# aig2.net
KiCad netlist of a schematic drawn in Altium Designer
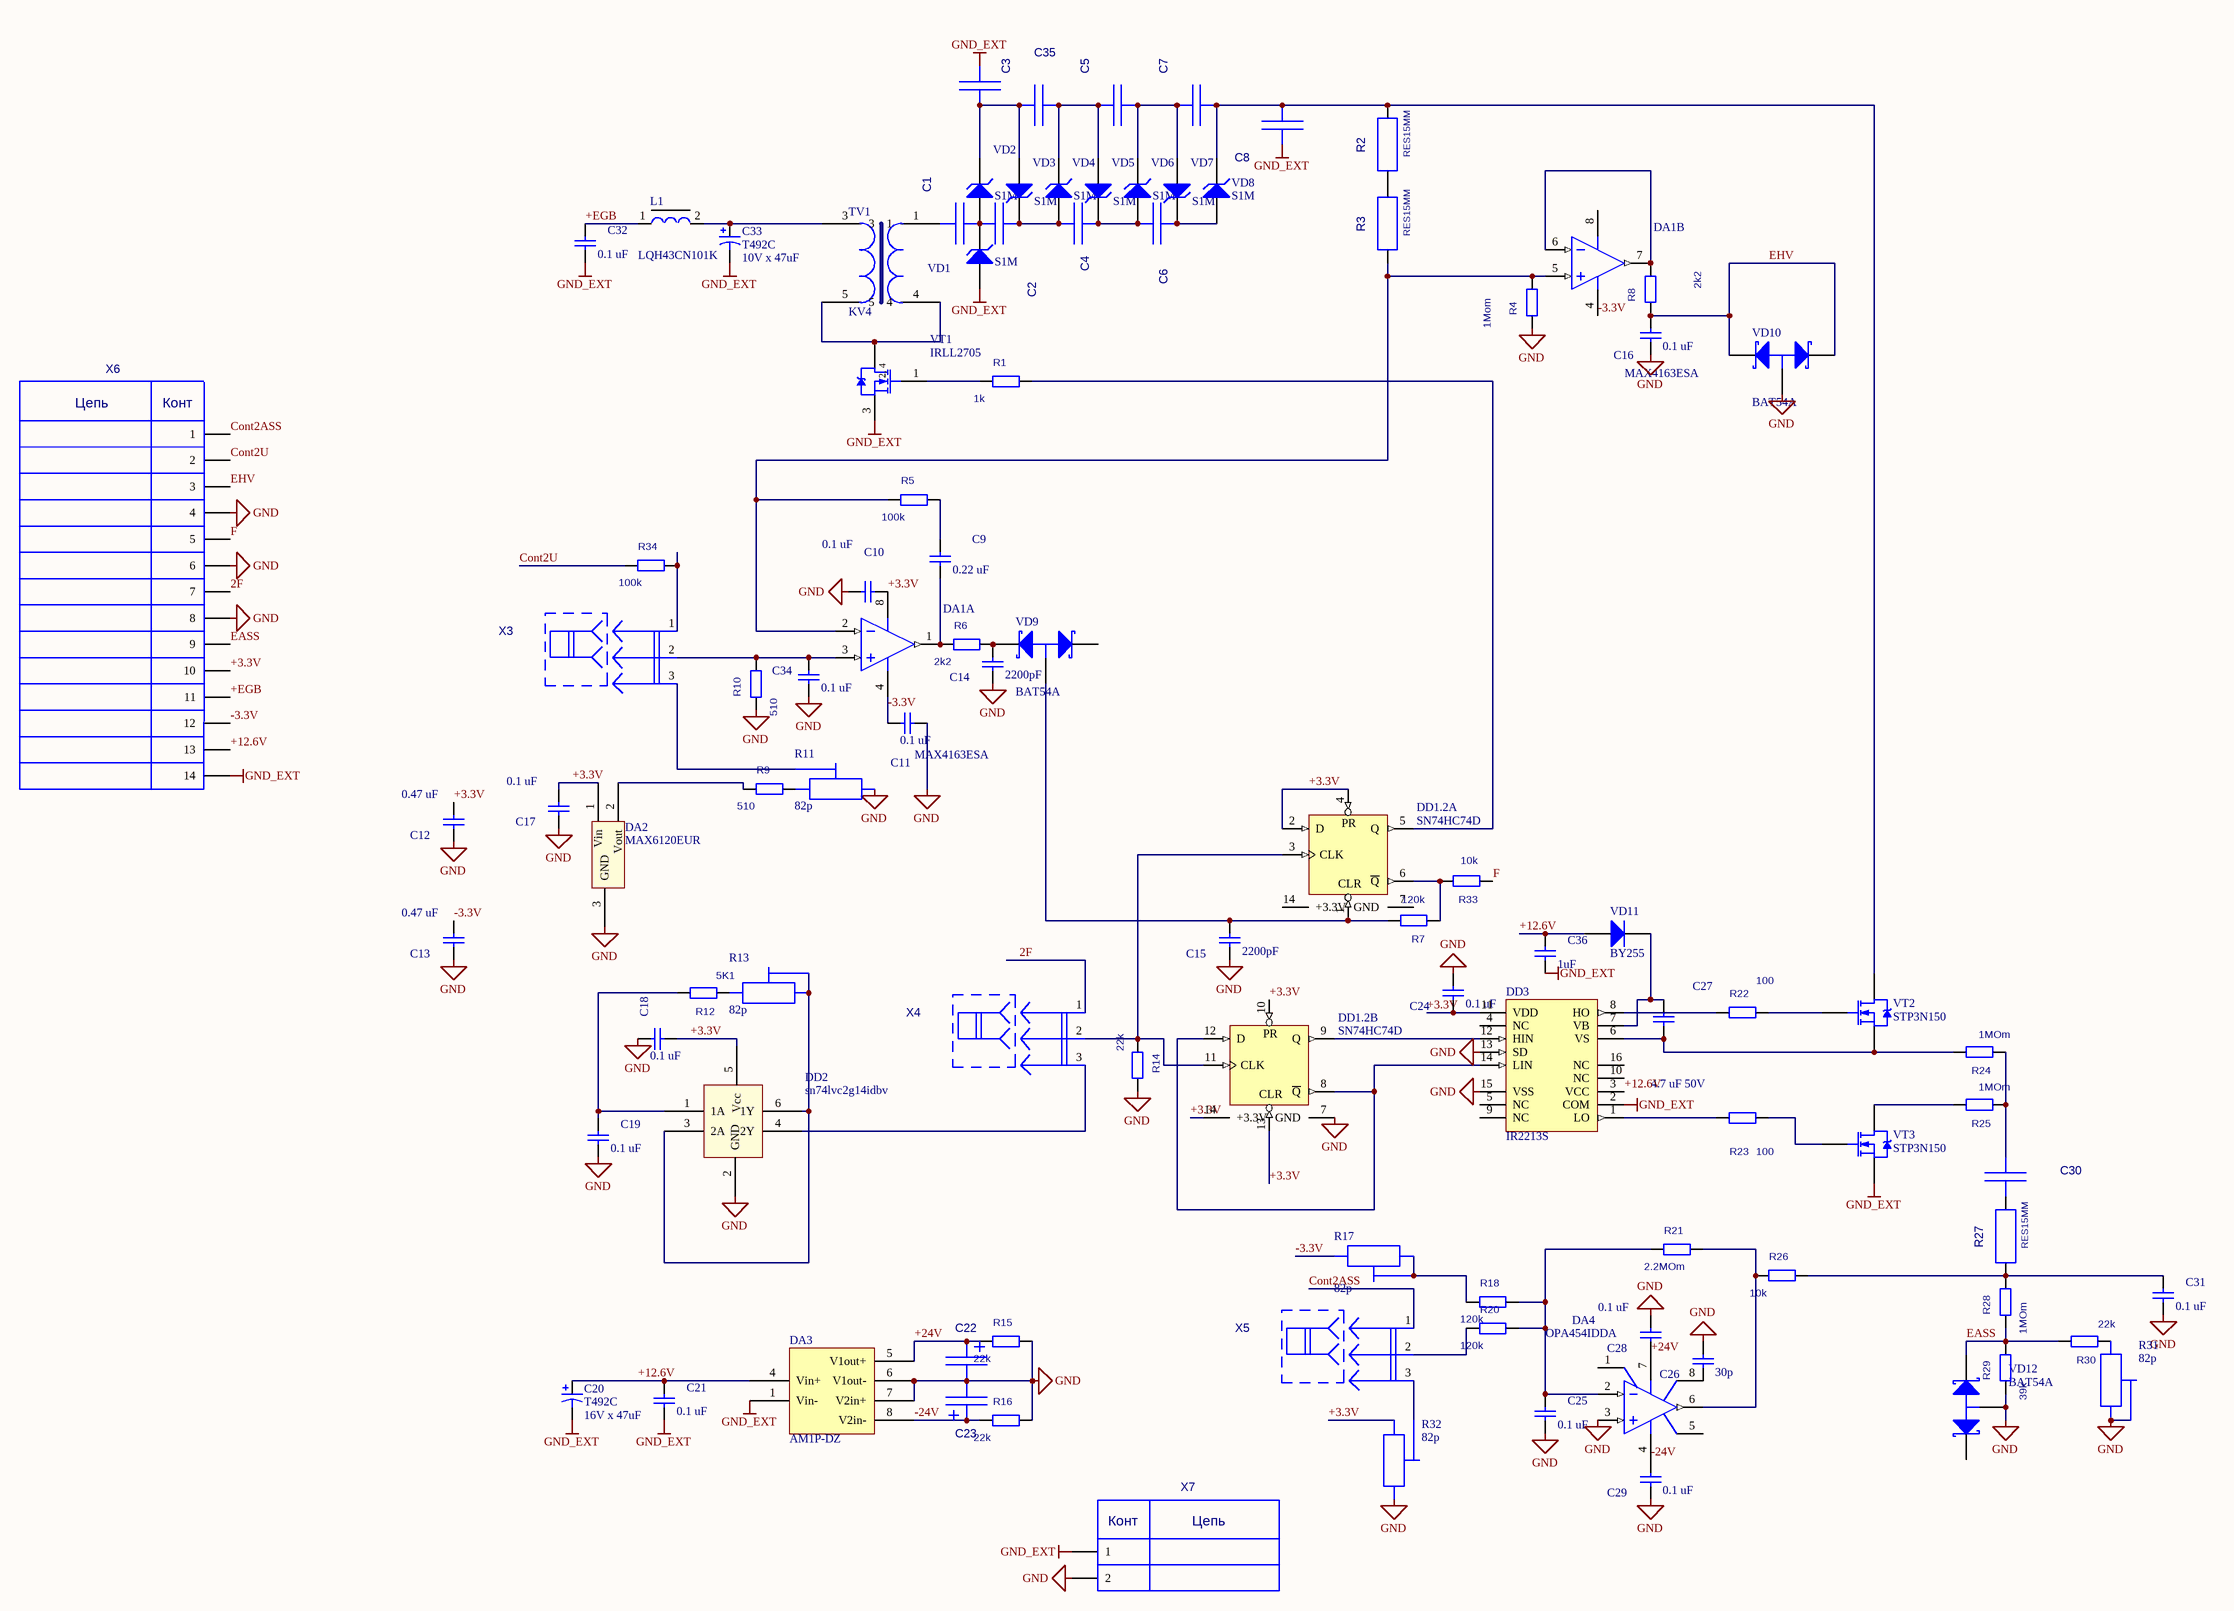
[diagram p0: aig2.SchDoc]

(export (version "E")
  (design (tool "Eeschema 10.0.6"))
  (components
    (comp (ref "C1") (value "CC1812") (footprint "CC1812") (libsource (lib "MyElements") (part "CC1812")))
    (comp (ref "C2") (value "CC1812") (footprint "CC1812") (libsource (lib "MyElements") (part "CC1812")))
    (comp (ref "C3") (value "CC1812") (footprint "CC1812") (libsource (lib "MyElements") (part "CC1812")))
    (comp (ref "C4") (value "CC1812") (footprint "CC1812") (libsource (lib "MyElements") (part "CC1812")))
    (comp (ref "C5") (value "CC1812") (footprint "CC1812") (libsource (lib "MyElements") (part "CC1812")))
    (comp (ref "C6") (value "CC1812") (footprint "CC1812") (libsource (lib "MyElements") (part "CC1812")))
    (comp (ref "C7") (value "CC1812") (footprint "CC1812") (libsource (lib "MyElements") (part "CC1812")))
    (comp (ref "C8") (value "CC1812") (footprint "CC1812") (libsource (lib "MyElements") (part "CC1812")))
    (comp (ref "C9")
      (value "0.22 uF")
      (footprint "CC0805")
      (description "Ceramic Chip Capacitor - Standard")
      (fields (field (name "Comment") "C0805") (field (name "PUBLISHER") "Altium Limited"))
      (libsource (lib "KEMET Chip Capacitor") (part "C0805"))
    )
    (comp (ref "C10")
      (value "0.1 uF")
      (footprint "CC0805")
      (description "Ceramic Chip Capacitor - Standard")
      (fields (field (name "Comment") "C0805") (field (name "PUBLISHER") "Altium Limited"))
      (libsource (lib "KEMET Chip Capacitor") (part "C0805"))
    )
    (comp (ref "C11")
      (value "0.1 uF")
      (footprint "CC0805")
      (description "Ceramic Chip Capacitor - Standard")
      (fields (field (name "Comment") "C0805") (field (name "PUBLISHER") "Altium Limited"))
      (libsource (lib "KEMET Chip Capacitor") (part "C0805"))
    )
    (comp (ref "C12")
      (value "0.47 uF")
      (footprint "CC0805")
      (description "Ceramic Chip Capacitor - Standard")
      (fields (field (name "Comment") "C0805") (field (name "PUBLISHER") "Altium Limited"))
      (libsource (lib "KEMET Chip Capacitor") (part "C0805"))
    )
    (comp (ref "C13")
      (value "0.47 uF")
      (footprint "CC0805")
      (description "Ceramic Chip Capacitor - Standard")
      (fields (field (name "Comment") "C0805") (field (name "PUBLISHER") "Altium Limited"))
      (libsource (lib "KEMET Chip Capacitor") (part "C0805"))
    )
    (comp (ref "C14")
      (value "2200pF")
      (footprint "CC0805")
      (description "Ceramic Chip Capacitor - Standard")
      (fields (field (name "Comment") "C0805") (field (name "PUBLISHER") "Altium Limited"))
      (libsource (lib "KEMET Chip Capacitor") (part "C0805"))
    )
    (comp (ref "C15")
      (value "2200pF")
      (footprint "CC0805")
      (description "Ceramic Chip Capacitor - Standard")
      (fields (field (name "Comment") "C0805") (field (name "PUBLISHER") "Altium Limited"))
      (libsource (lib "KEMET Chip Capacitor") (part "C0805"))
    )
    (comp (ref "C16")
      (value "0.1 uF")
      (footprint "CC0805")
      (description "Ceramic Chip Capacitor - Standard")
      (fields (field (name "Comment") "C0805") (field (name "PUBLISHER") "Altium Limited"))
      (libsource (lib "KEMET Chip Capacitor") (part "C0805"))
    )
    (comp (ref "C17")
      (value "0.1 uF")
      (footprint "CC0805")
      (description "Ceramic Chip Capacitor - Standard")
      (fields (field (name "Comment") "C0805") (field (name "PUBLISHER") "Altium Limited"))
      (libsource (lib "KEMET Chip Capacitor") (part "C0805"))
    )
    (comp (ref "C18")
      (value "0.1 uF")
      (footprint "CC0805")
      (description "Ceramic Chip Capacitor - Standard")
      (fields (field (name "Comment") "C0805") (field (name "PUBLISHER") "Altium Limited"))
      (libsource (lib "KEMET Chip Capacitor") (part "C0805"))
    )
    (comp (ref "C19")
      (value "0.1 uF")
      (footprint "CC0805")
      (description "Ceramic Chip Capacitor - Standard")
      (fields (field (name "Comment") "C0805") (field (name "PUBLISHER") "Altium Limited"))
      (libsource (lib "KEMET Chip Capacitor") (part "C0805"))
    )
    (comp (ref "C20")
      (value "T492C")
      (footprint "CAPASITOR C")
      (description "Solid Tantalum Chip Capacitor, T492 Series - CWR11 Style Per Mil-PRF-55365/8")
      (fields (field (name "ALTIUM_VALUE") "16V x 47uF") (field (name "PUBLISHER") "Altium Limited"))
      (libsource (lib "KEMET Chip Capacitor") (part "T492C"))
    )
    (comp (ref "C21")
      (value "0.1 uF")
      (footprint "CC0805")
      (description "Ceramic Chip Capacitor - Standard")
      (fields (field (name "Comment") "C0805") (field (name "PUBLISHER") "Altium Limited"))
      (libsource (lib "KEMET Chip Capacitor") (part "C0805"))
    )
    (comp (ref "C22")
      (value "CAPASITOR A")
      (footprint "CAPASITOR A")
      (libsource (lib "MyElements") (part "CAPASITOR A"))
    )
    (comp (ref "C23")
      (value "CAPASITOR A")
      (footprint "CAPASITOR A")
      (libsource (lib "MyElements") (part "CAPASITOR A"))
    )
    (comp (ref "C24")
      (value "0.1 uF")
      (footprint "CC0805")
      (description "Ceramic Chip Capacitor - Standard")
      (fields (field (name "Comment") "C0805") (field (name "PUBLISHER") "Altium Limited"))
      (libsource (lib "KEMET Chip Capacitor") (part "C0805"))
    )
    (comp (ref "C25")
      (value "0.1 uF")
      (footprint "CC0805")
      (description "Ceramic Chip Capacitor - Standard")
      (fields (field (name "Comment") "C0805") (field (name "PUBLISHER") "Altium Limited"))
      (libsource (lib "KEMET Chip Capacitor") (part "C0805"))
    )
    (comp (ref "C26")
      (value "30p")
      (footprint "CC0805")
      (description "Ceramic Chip Capacitor - Standard")
      (fields (field (name "Comment") "C0805") (field (name "PUBLISHER") "Altium Limited"))
      (libsource (lib "KEMET Chip Capacitor") (part "C0805"))
    )
    (comp (ref "C27")
      (value "4.7 uF 50V")
      (footprint "CC0805")
      (description "Ceramic Chip Capacitor - Standard")
      (fields (field (name "Comment") "C0805") (field (name "PUBLISHER") "Altium Limited"))
      (libsource (lib "KEMET Chip Capacitor") (part "C0805"))
    )
    (comp (ref "C28")
      (value "0.1 uF")
      (footprint "CC0805")
      (description "Ceramic Chip Capacitor - Standard")
      (fields (field (name "Comment") "C0805") (field (name "PUBLISHER") "Altium Limited"))
      (libsource (lib "KEMET Chip Capacitor") (part "C0805"))
    )
    (comp (ref "C29")
      (value "0.1 uF")
      (footprint "CC0805")
      (description "Ceramic Chip Capacitor - Standard")
      (fields (field (name "Comment") "C0805") (field (name "PUBLISHER") "Altium Limited"))
      (libsource (lib "KEMET Chip Capacitor") (part "C0805"))
    )
    (comp (ref "C30") (value "CC1812") (footprint "CC1812") (libsource (lib "MyElements") (part "CC1812")))
    (comp (ref "C31")
      (value "0.1 uF")
      (footprint "CC0805")
      (description "Ceramic Chip Capacitor - Standard")
      (fields (field (name "Comment") "C0805") (field (name "PUBLISHER") "Altium Limited"))
      (libsource (lib "KEMET Chip Capacitor") (part "C0805"))
    )
    (comp (ref "C32")
      (value "0.1 uF")
      (footprint "CC0805")
      (description "Ceramic Chip Capacitor - Standard")
      (fields (field (name "Comment") "C0805") (field (name "PUBLISHER") "Altium Limited"))
      (libsource (lib "KEMET Chip Capacitor") (part "C0805"))
    )
    (comp (ref "C33")
      (value "T492C")
      (footprint "CAPASITOR C")
      (description "Solid Tantalum Chip Capacitor, T492 Series - CWR11 Style Per Mil-PRF-55365/8")
      (fields (field (name "ALTIUM_VALUE") "10V x 47uF") (field (name "PUBLISHER") "Altium Limited"))
      (libsource (lib "KEMET Chip Capacitor") (part "T492C"))
    )
    (comp (ref "C34")
      (value "0.1 uF")
      (footprint "CC0805")
      (description "Ceramic Chip Capacitor - Standard")
      (fields (field (name "Comment") "C0805") (field (name "PUBLISHER") "Altium Limited"))
      (libsource (lib "KEMET Chip Capacitor") (part "C0805"))
    )
    (comp (ref "C35") (value "CC1812") (footprint "CC1812") (libsource (lib "MyElements") (part "CC1812")))
    (comp (ref "C36")
      (value "1uF")
      (footprint "CC0805")
      (description "Ceramic Chip Capacitor - Standard")
      (fields (field (name "Comment") "C0805") (field (name "PUBLISHER") "Altium Limited"))
      (libsource (lib "KEMET Chip Capacitor") (part "C0805"))
    )
    (comp (ref "DA1")
      (value "MAX4163ESA")
      (footprint "NSO8_N")
      (description "Dual Micropower, Single-Supply, Rail-to-Rail I/O Op Amp")
      (fields (field (name "PUBLISHER") "Altium Limited"))
      (libsource (lib "Maxim Operational Amplifier") (part "MAX4163ESA"))
    )
    (comp (ref "DA2")
      (value "MAX6120EUR")
      (footprint "sot23")
      (description "Микросхема")
      (libsource (lib "lgar") (part "MAX6120"))
    )
    (comp (ref "DA3")
      (value "AM1P-DZ")
      (footprint "Am1p")
      (description "DC/DC Перобразователь")
      (libsource (lib "lgar") (part "AM1P-DZ"))
    )
    (comp (ref "DA4")
      (value "OPA454IDDA")
      (footprint "182H_N")
      (description "Ultra-Low-Noise Precision Operational Amplifiers")
      (fields (field (name "PUBLISHER") "Altium Limited"))
      (libsource (lib "BB Operational Amplifier") (part "OPA27GU"))
    )
    (comp (ref "DD1.2")
      (value "SN74HC74D")
      (footprint "D014_N")
      (description "Dual D-Type Positive-Edge-Triggered Flip-Flop with Clear and Preset")
      (fields (field (name "PUBLISHER") "Altium Limited"))
      (libsource (lib "TI Logic Flip-Flop") (part "SN74HC74D"))
    )
    (comp (ref "DD2")
      (value "sn74lvc2g14idbv")
      (footprint "sot23-6_N")
      (description "Микросхема")
      (libsource (lib "lgar") (part "sn74lvc2g14idbv"))
    )
    (comp (ref "DD3")
      (value "IR2213S")
      (footprint "SOIC16_N")
      (description "High and Low Side Driver")
      (fields (field (name "PUBLISHER") "Altium Limited"))
      (libsource (lib "IR Interface Bridge Driver") (part "IR2113S"))
    )
    (comp (ref "L1")
      (value "LQH43CN101K")
      (footprint "1812")
      (description "Дроссель")
      (libsource (lib "lgar") (part "CDRH127"))
    )
    (comp (ref "R1")
      (value "1k")
      (footprint "RR0805")
      (description "R_0805")
      (libsource (lib "*") (part "R_0805"))
    )
    (comp (ref "R2") (value "RES15MM") (footprint "RES15MM") (libsource (lib "MyElements") (part "RES15MM")))
    (comp (ref "R3") (value "RES15MM") (footprint "RES15MM") (libsource (lib "MyElements") (part "RES15MM")))
    (comp (ref "R4")
      (value "1Mom")
      (footprint "RR0805")
      (description "R_0805")
      (libsource (lib "*") (part "R_0805"))
    )
    (comp (ref "R5")
      (value "100k")
      (footprint "RR0805")
      (description "R_0805")
      (libsource (lib "*") (part "R_0805"))
    )
    (comp (ref "R6")
      (value "2k2")
      (footprint "RR0805")
      (description "R_0805")
      (libsource (lib "*") (part "R_0805"))
    )
    (comp (ref "R7")
      (value "120k")
      (footprint "RR0805")
      (description "R_0805")
      (libsource (lib "*") (part "R_0805"))
    )
    (comp (ref "R8")
      (value "2k2")
      (footprint "RR0805")
      (description "R_0805")
      (libsource (lib "*") (part "R_0805"))
    )
    (comp (ref "R9")
      (value "510")
      (footprint "RR0805")
      (description "R_0805")
      (libsource (lib "*") (part "R_0805"))
    )
    (comp (ref "R10")
      (value "510")
      (footprint "RR0805")
      (description "R_0805")
      (libsource (lib "*") (part "R_0805"))
    )
    (comp (ref "R11")
      (value "82p")
      (footprint "82p")
      (description "Резистор")
      (libsource (lib "lgar") (part "82p"))
    )
    (comp (ref "R12")
      (value "5K1")
      (footprint "RR0805")
      (description "R_0805")
      (libsource (lib "*") (part "R_0805"))
    )
    (comp (ref "R13")
      (value "82p")
      (footprint "82p")
      (description "Резистор")
      (libsource (lib "lgar") (part "82p"))
    )
    (comp (ref "R14")
      (value "22k")
      (footprint "RR0805")
      (description "R_0805")
      (libsource (lib "*") (part "R_0805"))
    )
    (comp (ref "R15")
      (value "22k")
      (footprint "RR0805")
      (description "R_0805")
      (libsource (lib "*") (part "R_0805"))
    )
    (comp (ref "R16")
      (value "22k")
      (footprint "RR0805")
      (description "R_0805")
      (libsource (lib "*") (part "R_0805"))
    )
    (comp (ref "R17")
      (value "82p")
      (footprint "82p")
      (description "Резистор")
      (libsource (lib "lgar") (part "82p"))
    )
    (comp (ref "R18")
      (value "120k")
      (footprint "RR0805")
      (description "R_0805")
      (libsource (lib "*") (part "R_0805"))
    )
    (comp (ref "R20")
      (value "120k")
      (footprint "RR0805")
      (description "R_0805")
      (libsource (lib "*") (part "R_0805"))
    )
    (comp (ref "R21")
      (value "2.2MOm")
      (footprint "RR0805")
      (description "R_0805")
      (libsource (lib "*") (part "R_0805"))
    )
    (comp (ref "R22")
      (value "100")
      (footprint "RR0805")
      (description "R_0805")
      (libsource (lib "*") (part "R_0805"))
    )
    (comp (ref "R23")
      (value "100")
      (footprint "RR0805")
      (description "R_0805")
      (libsource (lib "*") (part "R_0805"))
    )
    (comp (ref "R24")
      (value "1MOm")
      (footprint "RR0805")
      (description "R_0805")
      (libsource (lib "*") (part "R_0805"))
    )
    (comp (ref "R25")
      (value "1MOm")
      (footprint "RR0805")
      (description "R_0805")
      (libsource (lib "*") (part "R_0805"))
    )
    (comp (ref "R26")
      (value "10k")
      (footprint "RR0805")
      (description "R_0805")
      (libsource (lib "*") (part "R_0805"))
    )
    (comp (ref "R27") (value "RES15MM") (footprint "RES15MM") (libsource (lib "MyElements") (part "RES15MM")))
    (comp (ref "R28")
      (value "1MOm")
      (footprint "RR0805")
      (description "R_0805")
      (libsource (lib "*") (part "R_0805"))
    )
    (comp (ref "R29")
      (value "39k")
      (footprint "RR0805")
      (description "R_0805")
      (libsource (lib "*") (part "R_0805"))
    )
    (comp (ref "R30")
      (value "22k")
      (footprint "RR0805")
      (description "R_0805")
      (libsource (lib "*") (part "R_0805"))
    )
    (comp (ref "R31")
      (value "82p")
      (footprint "82p")
      (description "Резистор")
      (libsource (lib "lgar") (part "82p"))
    )
    (comp (ref "R32")
      (value "82p")
      (footprint "82p")
      (description "Резистор")
      (libsource (lib "lgar") (part "82p"))
    )
    (comp (ref "R33")
      (value "10k")
      (footprint "RR0805")
      (description "R_0805")
      (libsource (lib "*") (part "R_0805"))
    )
    (comp (ref "R34")
      (value "100k")
      (footprint "RR0805")
      (description "R_0805")
      (libsource (lib "*") (part "R_0805"))
    )
    (comp (ref "TV1")
      (value "KV4")
      (footprint "kv4")
      (description "Трансформатор")
      (libsource (lib "lgar") (part "KV4"))
    )
    (comp (ref "VD1")
      (value "S1M")
      (footprint "DO214")
      (description "Silicon Zener Diode (3W)")
      (fields (field (name "PUBLISHER") "Altium Limited"))
      (libsource (lib "Vishay Telefunken Discrete Diode") (part "BZG03C10"))
    )
    (comp (ref "VD2")
      (value "S1M")
      (footprint "DO214")
      (description "Silicon Zener Diode (3W)")
      (fields (field (name "PUBLISHER") "Altium Limited"))
      (libsource (lib "Vishay Telefunken Discrete Diode") (part "BZG03C10"))
    )
    (comp (ref "VD3")
      (value "S1M")
      (footprint "DO214")
      (description "Silicon Zener Diode (3W)")
      (fields (field (name "PUBLISHER") "Altium Limited"))
      (libsource (lib "Vishay Telefunken Discrete Diode") (part "BZG03C10"))
    )
    (comp (ref "VD4")
      (value "S1M")
      (footprint "DO214")
      (description "Silicon Zener Diode (3W)")
      (fields (field (name "PUBLISHER") "Altium Limited"))
      (libsource (lib "Vishay Telefunken Discrete Diode") (part "BZG03C10"))
    )
    (comp (ref "VD5")
      (value "S1M")
      (footprint "DO214")
      (description "Silicon Zener Diode (3W)")
      (fields (field (name "PUBLISHER") "Altium Limited"))
      (libsource (lib "Vishay Telefunken Discrete Diode") (part "BZG03C10"))
    )
    (comp (ref "VD6")
      (value "S1M")
      (footprint "DO214")
      (description "Silicon Zener Diode (3W)")
      (fields (field (name "PUBLISHER") "Altium Limited"))
      (libsource (lib "Vishay Telefunken Discrete Diode") (part "BZG03C10"))
    )
    (comp (ref "VD7")
      (value "S1M")
      (footprint "DO214")
      (description "Silicon Zener Diode (3W)")
      (fields (field (name "PUBLISHER") "Altium Limited"))
      (libsource (lib "Vishay Telefunken Discrete Diode") (part "BZG03C10"))
    )
    (comp (ref "VD8")
      (value "S1M")
      (footprint "DO214")
      (description "Silicon Zener Diode (3W)")
      (fields (field (name "PUBLISHER") "Altium Limited"))
      (libsource (lib "Vishay Telefunken Discrete Diode") (part "BZG03C10"))
    )
    (comp (ref "VD9")
      (value "BAT54A")
      (footprint "SOT23_N")
      (description "Schottky Barrier Double Diode")
      (fields (field (name "PUBLISHER") "Altium Limited"))
      (libsource (lib "Philips Discrete Diode - Schottky") (part "BAT54A"))
    )
    (comp (ref "VD10")
      (value "BAT54A")
      (footprint "SOT23_N")
      (description "Schottky Barrier Double Diode")
      (fields (field (name "PUBLISHER") "Altium Limited"))
      (libsource (lib "Philips Discrete Diode - Schottky") (part "BAT54A"))
    )
    (comp (ref "VD11")
      (value "BY255")
      (footprint "SOD27")
      (description "Диод")
      (fields (field (name "PUBLISHER") "Altium Limited"))
      (libsource (lib "Philips Discrete Diode - Switching") (part "BZX79-B15"))
    )
    (comp (ref "VD12")
      (value "BAT54A")
      (footprint "SOT23_N")
      (description "Schottky Barrier Double Diode")
      (fields (field (name "PUBLISHER") "Altium Limited"))
      (libsource (lib "Philips Discrete Diode - Schottky") (part "BAT54A"))
    )
    (comp (ref "VT1")
      (value "IRLL2705")
      (footprint "SOT-223")
      (description "HEXFET Power MOSFET")
      (fields (field (name "PUBLISHER") "Altium Limited"))
      (libsource (lib "IR Discrete MOSFET - Power") (part "IRLL2705"))
    )
    (comp (ref "VT2")
      (value "STP3N150")
      (footprint "TO-220AB")
      (description "HEXFET N-Channel Power MOSFET")
      (fields (field (name "PUBLISHER") "Altium Limited"))
      (libsource (lib "IR Discrete MOSFET - Power") (part "IRF740"))
    )
    (comp (ref "VT3")
      (value "STP3N150")
      (footprint "TO-220AB")
      (description "HEXFET N-Channel Power MOSFET")
      (fields (field (name "PUBLISHER") "Altium Limited"))
      (libsource (lib "IR Discrete MOSFET - Power") (part "IRF740"))
    )
    (comp (ref "X3") (value "JP3") (footprint "PLS-3 2.54") (libsource (lib "MyElements") (part "JP3")))
    (comp (ref "X4") (value "JP3") (footprint "PLS-3 2.54") (libsource (lib "MyElements") (part "JP3")))
    (comp (ref "X5") (value "JP3") (footprint "PLS-3 2.54") (libsource (lib "MyElements") (part "JP3")))
    (comp (ref "X6") (value "IDC14M") (footprint "IDC14M") (libsource (lib "MyElements") (part "IDC14M")))
    (comp (ref "X7") (value "PLS-2") (footprint "PLS-2 2.54") (libsource (lib "MyElements") (part "PLS-2")))
  )
  (nets
    (net (code "1") (name "/+3.3V") (class "Default")
      (node (ref "C10") (pin "2") (pinfunction "2_2") (pintype "passive"))
      (node (ref "C12") (pin "1") (pinfunction "1_1") (pintype "passive"))
      (node (ref "C17") (pin "1") (pinfunction "1_1") (pintype "passive"))
      (node (ref "C18") (pin "1") (pinfunction "1_1") (pintype "passive"))
      (node (ref "C24") (pin "2") (pinfunction "2_2") (pintype "passive"))
      (node (ref "DA1") (pin "8") (pinfunction "VDD_8") (pintype "power_in"))
      (node (ref "DA2") (pin "1") (pinfunction "Vin_1") (pintype "passive"))
      (node (ref "DD1.2") (pin "10") (pinfunction "PR_10") (pintype "input"))
      (node (ref "DD1.2") (pin "13") (pinfunction "CLR_13") (pintype "input"))
      (node (ref "DD1.2") (pin "14") (pinfunction "+3.3V_14") (pintype "power_in"))
      (node (ref "DD1.2") (pin "2") (pinfunction "D_2") (pintype "input"))
      (node (ref "DD1.2") (pin "4") (pinfunction "PR_4") (pintype "input"))
      (node (ref "DD2") (pin "5") (pinfunction "Vcc_5") (pintype "passive"))
      (node (ref "DD3") (pin "11") (pinfunction "VDD_11") (pintype "power_in"))
      (node (ref "R32") (pin "1") (pinfunction "I/O1_1") (pintype "passive"))
      (node (ref "X6") (pin "10") (pinfunction "10_10") (pintype "passive"))
    )
    (net (code "2") (name "/+12.6V") (class "Default")
      (node (ref "C20") (pin "1") (pinfunction "1_1") (pintype "passive"))
      (node (ref "C21") (pin "2") (pinfunction "2_2") (pintype "passive"))
      (node (ref "C36") (pin "2") (pinfunction "2_2") (pintype "passive"))
      (node (ref "DA3") (pin "4") (pinfunction "Vin+_4") (pintype "power_in"))
      (node (ref "DD3") (pin "3") (pinfunction "VCC_3") (pintype "power_in"))
      (node (ref "VD11") (pin "1") (pinfunction "A_1") (pintype "passive"))
      (node (ref "X6") (pin "13") (pinfunction "13_13") (pintype "passive"))
    )
    (net (code "3") (name "/+24V") (class "Default")
      (node (ref "C22") (pin "1") (pinfunction "i/o_1") (pintype "passive"))
      (node (ref "C28") (pin "2") (pinfunction "2_2") (pintype "passive"))
      (node (ref "DA3") (pin "5") (pinfunction "V1out+_5") (pintype "power_in"))
      (node (ref "DA4") (pin "7") (pinfunction "V+_7") (pintype "power_in"))
      (node (ref "R15") (pin "1") (pintype "passive"))
    )
    (net (code "4") (name "/+EGB") (class "Default")
      (node (ref "C32") (pin "2") (pinfunction "2_2") (pintype "passive"))
      (node (ref "L1") (pin "1") (pinfunction "1_1") (pintype "passive"))
      (node (ref "X6") (pin "11") (pinfunction "11_11") (pintype "passive"))
    )
    (net (code "5") (name "/-3.3V") (class "Default")
      (node (ref "C11") (pin "2") (pinfunction "2_2") (pintype "passive"))
      (node (ref "C13") (pin "1") (pinfunction "1_1") (pintype "passive"))
      (node (ref "DA1") (pin "4") (pinfunction "VSS_4") (pintype "power_in"))
      (node (ref "R17") (pin "3") (pinfunction "I/O_3") (pintype "passive"))
      (node (ref "X6") (pin "12") (pinfunction "12_12") (pintype "passive"))
    )
    (net (code "6") (name "/-24V") (class "Default")
      (node (ref "C23") (pin "1") (pinfunction "i/o_1") (pintype "passive"))
      (node (ref "C29") (pin "1") (pinfunction "1_1") (pintype "passive"))
      (node (ref "DA3") (pin "8") (pinfunction "V2in-_8") (pintype "power_in"))
      (node (ref "DA4") (pin "4") (pinfunction "V-_4") (pintype "power_in"))
      (node (ref "R16") (pin "1") (pintype "passive"))
    )
    (net (code "7") (name "/2F") (class "Default")
      (node (ref "X4") (pin "1") (pinfunction "I/O1_1") (pintype "passive"))
      (node (ref "X6") (pin "7") (pinfunction "7_7") (pintype "passive"))
    )
    (net (code "8") (name "/Cont2ASS") (class "Default")
      (node (ref "X5") (pin "1") (pinfunction "I/O1_1") (pintype "passive"))
      (node (ref "X6") (pin "1") (pinfunction "1_1") (pintype "passive"))
    )
    (net (code "9") (name "/Cont2U") (class "Default")
      (node (ref "R34") (pin "1") (pintype "passive"))
      (node (ref "X6") (pin "2") (pinfunction "2_2") (pintype "passive"))
    )
    (net (code "10") (name "/EASS") (class "Default")
      (node (ref "R28") (pin "1") (pintype "passive"))
      (node (ref "R29") (pin "2") (pintype "passive"))
      (node (ref "R30") (pin "2") (pintype "passive"))
      (node (ref "VD12") (pin "1") (pinfunction "K1_1") (pintype "passive"))
      (node (ref "X6") (pin "9") (pinfunction "9_9") (pintype "passive"))
    )
    (net (code "11") (name "/EHV") (class "Default")
      (node (ref "C16") (pin "1") (pinfunction "1_1") (pintype "passive"))
      (node (ref "R8") (pin "1") (pintype "passive"))
      (node (ref "VD10") (pin "1") (pinfunction "K1_1") (pintype "passive"))
      (node (ref "VD10") (pin "2") (pinfunction "K2_2") (pintype "passive"))
      (node (ref "X6") (pin "3") (pinfunction "3_3") (pintype "passive"))
    )
    (net (code "12") (name "/F") (class "Default")
      (node (ref "R33") (pin "1") (pintype "passive"))
      (node (ref "X6") (pin "5") (pinfunction "5_5") (pintype "passive"))
    )
    (net (code "13") (name "GND") (class "Default")
      (node (ref "C10") (pin "1") (pinfunction "1_1") (pintype "passive"))
      (node (ref "C11") (pin "1") (pinfunction "1_1") (pintype "passive"))
      (node (ref "C12") (pin "2") (pinfunction "2_2") (pintype "passive"))
      (node (ref "C13") (pin "2") (pinfunction "2_2") (pintype "passive"))
      (node (ref "C14") (pin "2") (pinfunction "2_2") (pintype "passive"))
      (node (ref "C15") (pin "2") (pinfunction "2_2") (pintype "passive"))
      (node (ref "C16") (pin "2") (pinfunction "2_2") (pintype "passive"))
      (node (ref "C17") (pin "2") (pinfunction "2_2") (pintype "passive"))
      (node (ref "C18") (pin "2") (pinfunction "2_2") (pintype "passive"))
      (node (ref "C19") (pin "1") (pinfunction "1_1") (pintype "passive"))
      (node (ref "C22") (pin "2") (pinfunction "i/o1_2") (pintype "passive"))
      (node (ref "C23") (pin "2") (pinfunction "i/o1_2") (pintype "passive"))
      (node (ref "C24") (pin "1") (pinfunction "1_1") (pintype "passive"))
      (node (ref "C25") (pin "1") (pinfunction "1_1") (pintype "passive"))
      (node (ref "C26") (pin "1") (pinfunction "1_1") (pintype "passive"))
      (node (ref "C28") (pin "1") (pinfunction "1_1") (pintype "passive"))
      (node (ref "C29") (pin "2") (pinfunction "2_2") (pintype "passive"))
      (node (ref "C31") (pin "1") (pinfunction "1_1") (pintype "passive"))
      (node (ref "C34") (pin "1") (pinfunction "1_1") (pintype "passive"))
      (node (ref "DA2") (pin "3") (pinfunction "GND_3") (pintype "passive"))
      (node (ref "DA3") (pin "6") (pinfunction "V1out-_6") (pintype "power_in"))
      (node (ref "DA3") (pin "7") (pinfunction "V2in+_7") (pintype "power_in"))
      (node (ref "DA4") (pin "3") (pinfunction "IN+_3") (pintype "input"))
      (node (ref "DD1.2") (pin "7") (pinfunction "GND_7") (pintype "power_in"))
      (node (ref "DD2") (pin "2") (pinfunction "GND_2") (pintype "passive"))
      (node (ref "DD3") (pin "13") (pinfunction "SD_13") (pintype "input"))
      (node (ref "DD3") (pin "15") (pinfunction "VSS_15") (pintype "power_in"))
      (node (ref "R10") (pin "1") (pintype "passive"))
      (node (ref "R11") (pin "3") (pinfunction "I/O_3") (pintype "passive"))
      (node (ref "R14") (pin "2") (pintype "passive"))
      (node (ref "R15") (pin "2") (pintype "passive"))
      (node (ref "R16") (pin "2") (pintype "passive"))
      (node (ref "R29") (pin "1") (pintype "passive"))
      (node (ref "R31") (pin "1") (pinfunction "I/O1_1") (pintype "passive"))
      (node (ref "R31") (pin "2") (pinfunction "I/O0_2") (pintype "passive"))
      (node (ref "R32") (pin "3") (pinfunction "I/O_3") (pintype "passive"))
      (node (ref "R4") (pin "1") (pintype "passive"))
      (node (ref "VD10") (pin "3") (pinfunction "A_3") (pintype "passive"))
      (node (ref "VD12") (pin "3") (pinfunction "A_3") (pintype "passive"))
      (node (ref "X6") (pin "4") (pinfunction "4_4") (pintype "passive"))
      (node (ref "X6") (pin "6") (pinfunction "6_6") (pintype "passive"))
      (node (ref "X6") (pin "8") (pinfunction "8_8") (pintype "passive"))
      (node (ref "X7") (pin "2") (pinfunction "2_2") (pintype "passive"))
    )
    (net (code "14") (name "GND_EXT") (class "Default")
      (node (ref "C20") (pin "2") (pinfunction "2_2") (pintype "passive"))
      (node (ref "C21") (pin "1") (pinfunction "1_1") (pintype "passive"))
      (node (ref "C32") (pin "1") (pinfunction "1_1") (pintype "passive"))
      (node (ref "C33") (pin "2") (pinfunction "2_2") (pintype "passive"))
      (node (ref "C35") (pin "2") (pinfunction "i/o1_2") (pintype "passive"))
      (node (ref "C36") (pin "1") (pinfunction "1_1") (pintype "passive"))
      (node (ref "C8") (pin "1") (pinfunction "i/o_1") (pintype "passive"))
      (node (ref "DA3") (pin "1") (pinfunction "Vin-_1") (pintype "power_in"))
      (node (ref "DD3") (pin "2") (pinfunction "COM_2") (pintype "power_in"))
      (node (ref "VD1") (pin "1") (pinfunction "A_1") (pintype "passive"))
      (node (ref "VT1") (pin "3") (pinfunction "S_3") (pintype "passive"))
      (node (ref "VT3") (pin "3") (pinfunction "S_3") (pintype "passive"))
      (node (ref "X6") (pin "14") (pinfunction "14_14") (pintype "passive"))
      (node (ref "X7") (pin "1") (pinfunction "1_1") (pintype "passive"))
    )
    (net (code "15") (name "Net-(C1-i{slash}o)") (class "Default")
      (node (ref "C1") (pin "1") (pinfunction "i/o_1") (pintype "passive"))
      (node (ref "TV1") (pin "1") (pinfunction "1_1") (pintype "passive"))
    )
    (net (code "16") (name "Net-(C1-i{slash}o1)") (class "Default")
      (node (ref "C1") (pin "2") (pinfunction "i/o1_2") (pintype "passive"))
      (node (ref "C2") (pin "1") (pinfunction "i/o_1") (pintype "passive"))
      (node (ref "VD1") (pin "2") (pinfunction "K_2") (pintype "passive"))
      (node (ref "VD2") (pin "1") (pinfunction "A_1") (pintype "passive"))
    )
    (net (code "17") (name "Net-(C2-i{slash}o1)") (class "Default")
      (node (ref "C2") (pin "2") (pinfunction "i/o1_2") (pintype "passive"))
      (node (ref "C4") (pin "1") (pinfunction "i/o_1") (pintype "passive"))
      (node (ref "VD3") (pin "2") (pinfunction "K_2") (pintype "passive"))
      (node (ref "VD4") (pin "1") (pinfunction "A_1") (pintype "passive"))
    )
    (net (code "18") (name "Net-(C3-i{slash}o)") (class "Default")
      (node (ref "C3") (pin "1") (pinfunction "i/o_1") (pintype "passive"))
      (node (ref "C35") (pin "1") (pinfunction "i/o_1") (pintype "passive"))
      (node (ref "VD2") (pin "2") (pinfunction "K_2") (pintype "passive"))
      (node (ref "VD3") (pin "1") (pinfunction "A_1") (pintype "passive"))
    )
    (net (code "19") (name "Net-(C3-i{slash}o1)") (class "Default")
      (node (ref "C3") (pin "2") (pinfunction "i/o1_2") (pintype "passive"))
      (node (ref "C5") (pin "1") (pinfunction "i/o_1") (pintype "passive"))
      (node (ref "VD4") (pin "2") (pinfunction "K_2") (pintype "passive"))
      (node (ref "VD5") (pin "1") (pinfunction "A_1") (pintype "passive"))
    )
    (net (code "20") (name "Net-(C4-i{slash}o1)") (class "Default")
      (node (ref "C4") (pin "2") (pinfunction "i/o1_2") (pintype "passive"))
      (node (ref "C6") (pin "1") (pinfunction "i/o_1") (pintype "passive"))
      (node (ref "VD5") (pin "2") (pinfunction "K_2") (pintype "passive"))
      (node (ref "VD6") (pin "1") (pinfunction "A_1") (pintype "passive"))
    )
    (net (code "21") (name "Net-(C5-i{slash}o1)") (class "Default")
      (node (ref "C5") (pin "2") (pinfunction "i/o1_2") (pintype "passive"))
      (node (ref "C7") (pin "1") (pinfunction "i/o_1") (pintype "passive"))
      (node (ref "VD6") (pin "2") (pinfunction "K_2") (pintype "passive"))
      (node (ref "VD7") (pin "1") (pinfunction "A_1") (pintype "passive"))
    )
    (net (code "22") (name "Net-(C6-i{slash}o1)") (class "Default")
      (node (ref "C6") (pin "2") (pinfunction "i/o1_2") (pintype "passive"))
      (node (ref "VD7") (pin "2") (pinfunction "K_2") (pintype "passive"))
      (node (ref "VD8") (pin "1") (pinfunction "A_1") (pintype "passive"))
    )
    (net (code "23") (name "Net-(C7-i{slash}o1)") (class "Default")
      (node (ref "C7") (pin "2") (pinfunction "i/o1_2") (pintype "passive"))
      (node (ref "C8") (pin "2") (pinfunction "i/o1_2") (pintype "passive"))
      (node (ref "R2") (pin "2") (pinfunction "I/O1_2") (pintype "passive"))
      (node (ref "VD8") (pin "2") (pinfunction "K_2") (pintype "passive"))
      (node (ref "VT2") (pin "2") (pinfunction "D_2") (pintype "passive"))
    )
    (net (code "24") (name "Net-(C9-Pad1)") (class "Default")
      (node (ref "C9") (pin "1") (pinfunction "1_1") (pintype "passive"))
      (node (ref "R5") (pin "2") (pintype "passive"))
    )
    (net (code "25") (name "Net-(C26-Pad2)") (class "Default")
      (node (ref "C26") (pin "2") (pinfunction "2_2") (pintype "passive"))
      (node (ref "DA4") (pin "8") (pinfunction "VOSTRIM_8") (pintype "passive"))
    )
    (net (code "26") (name "Net-(C30-i{slash}o)") (class "Default")
      (node (ref "C30") (pin "1") (pinfunction "i/o_1") (pintype "passive"))
      (node (ref "R24") (pin "1") (pintype "passive"))
      (node (ref "R25") (pin "1") (pintype "passive"))
    )
    (net (code "27") (name "Net-(C30-i{slash}o1)") (class "Default")
      (node (ref "C30") (pin "2") (pinfunction "i/o1_2") (pintype "passive"))
      (node (ref "R27") (pin "2") (pinfunction "I/O1_2") (pintype "passive"))
    )
    (net (code "28") (name "Net-(C33-Pad1)") (class "Default")
      (node (ref "C33") (pin "1") (pinfunction "1_1") (pintype "passive"))
      (node (ref "L1") (pin "2") (pinfunction "2_2") (pintype "passive"))
      (node (ref "TV1") (pin "3") (pinfunction "3_3") (pintype "passive"))
    )
    (net (code "29") (name "Net-(DA1A-IN+)") (class "Default")
      (node (ref "C34") (pin "2") (pinfunction "2_2") (pintype "passive"))
      (node (ref "DA1") (pin "3") (pinfunction "IN+_3") (pintype "input"))
      (node (ref "R10") (pin "2") (pintype "passive"))
      (node (ref "X3") (pin "2") (pinfunction "I/O2_2") (pintype "passive"))
    )
    (net (code "30") (name "Net-(DA1A-IN-)") (class "Default")
      (node (ref "DA1") (pin "2") (pinfunction "IN-_2") (pintype "input"))
      (node (ref "DA1") (pin "5") (pinfunction "IN+_5") (pintype "input"))
      (node (ref "R3") (pin "1") (pinfunction "I/O0_1") (pintype "passive"))
      (node (ref "R4") (pin "2") (pintype "passive"))
      (node (ref "R5") (pin "1") (pintype "passive"))
    )
    (net (code "31") (name "Net-(DA1A-OUT)") (class "Default")
      (node (ref "C9") (pin "2") (pinfunction "2_2") (pintype "passive"))
      (node (ref "DA1") (pin "1") (pinfunction "OUT_1") (pintype "output"))
      (node (ref "R6") (pin "1") (pintype "passive"))
    )
    (net (code "32") (name "Net-(DA1B-IN-)") (class "Default")
      (node (ref "DA1") (pin "6") (pinfunction "IN-_6") (pintype "input"))
      (node (ref "DA1") (pin "7") (pinfunction "OUT_7") (pintype "output"))
      (node (ref "R8") (pin "2") (pintype "passive"))
    )
    (net (code "33") (name "Net-(DA2-Vout)") (class "Default")
      (node (ref "DA2") (pin "2") (pinfunction "Vout_2") (pintype "passive"))
      (node (ref "R9") (pin "1") (pintype "passive"))
    )
    (net (code "34") (name "Net-(DA4-IN-)") (class "Default")
      (node (ref "C25") (pin "2") (pinfunction "2_2") (pintype "passive"))
      (node (ref "DA4") (pin "2") (pinfunction "IN-_2") (pintype "input"))
      (node (ref "R18") (pin "2") (pintype "passive"))
      (node (ref "R20") (pin "2") (pintype "passive"))
      (node (ref "R21") (pin "1") (pintype "passive"))
    )
    (net (code "35") (name "Net-(DA4-OUT)") (class "Default")
      (node (ref "DA4") (pin "6") (pinfunction "OUT_6") (pintype "output"))
      (node (ref "R21") (pin "2") (pintype "passive"))
      (node (ref "R26") (pin "1") (pintype "passive"))
    )
    (net (code "36") (name "Net-(DD1.2A-CLK)") (class "Default")
      (node (ref "DD1.2") (pin "11") (pinfunction "CLK_11") (pintype "input"))
      (node (ref "DD1.2") (pin "3") (pinfunction "CLK_3") (pintype "input"))
      (node (ref "R14") (pin "1") (pintype "passive"))
      (node (ref "X4") (pin "2") (pinfunction "I/O2_2") (pintype "passive"))
    )
    (net (code "37") (name "Net-(DD1.2A-CLR)") (class "Default")
      (node (ref "C15") (pin "1") (pinfunction "1_1") (pintype "passive"))
      (node (ref "DD1.2") (pin "1") (pinfunction "CLR_1") (pintype "input"))
      (node (ref "R7") (pin "2") (pintype "passive"))
      (node (ref "VD9") (pin "3") (pinfunction "A_3") (pintype "passive"))
    )
    (net (code "38") (name "Net-(DD1.2A-Q)") (class "Default")
      (node (ref "DD1.2") (pin "5") (pinfunction "Q_5") (pintype "output"))
      (node (ref "R1") (pin "2") (pintype "passive"))
    )
    (net (code "39") (name "Net-(DD1.2A-~{Q})") (class "Default")
      (node (ref "DD1.2") (pin "6") (pinfunction "~{Q}_6") (pintype "output"))
      (node (ref "R33") (pin "2") (pintype "passive"))
      (node (ref "R7") (pin "1") (pintype "passive"))
    )
    (net (code "40") (name "Net-(DD1.2B-D)") (class "Default")
      (node (ref "DD1.2") (pin "12") (pinfunction "D_12") (pintype "input"))
      (node (ref "DD1.2") (pin "8") (pinfunction "~{Q}_8") (pintype "output"))
      (node (ref "DD3") (pin "14") (pinfunction "LIN_14") (pintype "input"))
    )
    (net (code "41") (name "Net-(DD1.2B-Q)") (class "Default")
      (node (ref "DD1.2") (pin "9") (pinfunction "Q_9") (pintype "output"))
      (node (ref "DD3") (pin "12") (pinfunction "HIN_12") (pintype "input"))
    )
    (net (code "42") (name "Net-(DD2-1A)") (class "Default")
      (node (ref "C19") (pin "2") (pinfunction "2_2") (pintype "passive"))
      (node (ref "DD2") (pin "1") (pinfunction "1A_1") (pintype "passive"))
      (node (ref "R12") (pin "2") (pintype "passive"))
    )
    (net (code "43") (name "Net-(DD2-1Y)") (class "Default")
      (node (ref "DD2") (pin "3") (pinfunction "2A_3") (pintype "passive"))
      (node (ref "DD2") (pin "6") (pinfunction "1Y_6") (pintype "passive"))
      (node (ref "R13") (pin "1") (pinfunction "I/O1_1") (pintype "passive"))
      (node (ref "R13") (pin "2") (pinfunction "I/O0_2") (pintype "passive"))
    )
    (net (code "44") (name "Net-(DD2-2Y)") (class "Default")
      (node (ref "DD2") (pin "4") (pinfunction "2Y_4") (pintype "passive"))
      (node (ref "X4") (pin "3") (pinfunction "I/O3_3") (pintype "passive"))
    )
    (net (code "45") (name "Net-(DD3-HO)") (class "Default")
      (node (ref "DD3") (pin "8") (pinfunction "HO_8") (pintype "output"))
      (node (ref "R22") (pin "1") (pintype "passive"))
    )
    (net (code "46") (name "Net-(DD3-LO)") (class "Default")
      (node (ref "DD3") (pin "1") (pinfunction "LO_1") (pintype "output"))
      (node (ref "R23") (pin "1") (pintype "passive"))
    )
    (net (code "47") (name "Net-(DD3-VB)") (class "Default")
      (node (ref "C27") (pin "2") (pinfunction "2_2") (pintype "passive"))
      (node (ref "DD3") (pin "7") (pinfunction "VB_7") (pintype "power_in"))
      (node (ref "VD11") (pin "2") (pinfunction "K_2") (pintype "passive"))
    )
    (net (code "48") (name "Net-(DD3-VS)") (class "Default")
      (node (ref "C27") (pin "1") (pinfunction "1_1") (pintype "passive"))
      (node (ref "DD3") (pin "6") (pinfunction "VS_6") (pintype "power_in"))
      (node (ref "R24") (pin "2") (pintype "passive"))
      (node (ref "VT2") (pin "3") (pinfunction "S_3") (pintype "passive"))
    )
    (net (code "49") (name "Net-(R2-I{slash}O0)") (class "Default")
      (node (ref "R2") (pin "1") (pinfunction "I/O0_1") (pintype "passive"))
      (node (ref "R3") (pin "2") (pinfunction "I/O1_2") (pintype "passive"))
    )
    (net (code "50") (name "Net-(R11-I{slash}O0)") (class "Default")
      (node (ref "R11") (pin "2") (pinfunction "I/O0_2") (pintype "passive"))
      (node (ref "X3") (pin "3") (pinfunction "I/O3_3") (pintype "passive"))
    )
    (net (code "51") (name "Net-(R11-I{slash}O1)") (class "Default")
      (node (ref "R11") (pin "1") (pinfunction "I/O1_1") (pintype "passive"))
      (node (ref "R9") (pin "2") (pintype "passive"))
    )
    (net (code "52") (name "Net-(R13-I{slash}O)") (class "Default")
      (node (ref "R12") (pin "1") (pintype "passive"))
      (node (ref "R13") (pin "3") (pinfunction "I/O_3") (pintype "passive"))
    )
    (net (code "53") (name "Net-(R17-I{slash}O0)") (class "Default")
      (node (ref "R17") (pin "1") (pinfunction "I/O1_1") (pintype "passive"))
      (node (ref "R17") (pin "2") (pinfunction "I/O0_2") (pintype "passive"))
      (node (ref "R18") (pin "1") (pintype "passive"))
    )
    (net (code "54") (name "Net-(R27-I{slash}O0)") (class "Default")
      (node (ref "C31") (pin "2") (pinfunction "2_2") (pintype "passive"))
      (node (ref "R26") (pin "2") (pintype "passive"))
      (node (ref "R27") (pin "1") (pinfunction "I/O0_1") (pintype "passive"))
      (node (ref "R28") (pin "2") (pintype "passive"))
    )
    (net (code "55") (name "Net-(R31-I{slash}O)") (class "Default")
      (node (ref "R30") (pin "1") (pintype "passive"))
      (node (ref "R31") (pin "3") (pinfunction "I/O_3") (pintype "passive"))
    )
    (net (code "56") (name "Net-(R32-I{slash}O0)") (class "Default")
      (node (ref "R32") (pin "2") (pinfunction "I/O0_2") (pintype "passive"))
      (node (ref "X5") (pin "3") (pinfunction "I/O3_3") (pintype "passive"))
    )
    (net (code "57") (name "Net-(TV1-Pad4)") (class "Default")
      (node (ref "TV1") (pin "4") (pinfunction "4_4") (pintype "passive"))
      (node (ref "TV1") (pin "5") (pinfunction "5_5") (pintype "passive"))
      (node (ref "VT1") (pin "2") (pinfunction "D_2") (pintype "passive"))
      (node (ref "VT1") (pin "4") (pinfunction "D_4") (pintype "passive"))
    )
    (net (code "58") (name "Net-(VD9-K1)") (class "Default")
      (node (ref "C14") (pin "1") (pinfunction "1_1") (pintype "passive"))
      (node (ref "R6") (pin "2") (pintype "passive"))
      (node (ref "VD9") (pin "1") (pinfunction "K1_1") (pintype "passive"))
    )
    (net (code "59") (name "Net-(VT1-G)") (class "Default")
      (node (ref "R1") (pin "1") (pintype "passive"))
      (node (ref "VT1") (pin "1") (pinfunction "G_1") (pintype "passive"))
    )
    (net (code "60") (name "Net-(VT2-G)") (class "Default")
      (node (ref "R22") (pin "2") (pintype "passive"))
      (node (ref "VT2") (pin "1") (pinfunction "G_1") (pintype "passive"))
    )
    (net (code "61") (name "Net-(VT3-D)") (class "Default")
      (node (ref "R25") (pin "2") (pintype "passive"))
      (node (ref "VT3") (pin "2") (pinfunction "D_2") (pintype "passive"))
    )
    (net (code "62") (name "Net-(VT3-G)") (class "Default")
      (node (ref "R23") (pin "2") (pintype "passive"))
      (node (ref "VT3") (pin "1") (pinfunction "G_1") (pintype "passive"))
    )
    (net (code "63") (name "Net-(X3-I{slash}O1)") (class "Default")
      (node (ref "R34") (pin "2") (pintype "passive"))
      (node (ref "X3") (pin "1") (pinfunction "I/O1_1") (pintype "passive"))
    )
    (net (code "64") (name "Net-(X5-I{slash}O2)") (class "Default")
      (node (ref "R20") (pin "1") (pintype "passive"))
      (node (ref "X5") (pin "2") (pinfunction "I/O2_2") (pintype "passive"))
    )
    (net (code "65") (name "unconnected-(DA1B-VDD-Pad8)") (class "Default")
      (node (ref "DA1") (pin "8") (pinfunction "VDD_8") (pintype "power_in"))
    )
    (net (code "66") (name "unconnected-(DA4-NC-Pad5)") (class "Default")
      (node (ref "DA4") (pin "5") (pinfunction "NC_5") (pintype "passive"))
    )
    (net (code "67") (name "unconnected-(DA4-VOSTRIM-Pad1)") (class "Default")
      (node (ref "DA4") (pin "1") (pinfunction "VOSTRIM_1") (pintype "passive"))
    )
    (net (code "68") (name "unconnected-(DD1.2A-+3.3V-Pad14)") (class "Default")
      (node (ref "DD1.2") (pin "14") (pinfunction "+3.3V_14") (pintype "power_in"))
    )
    (net (code "69") (name "unconnected-(DD1.2A-GND-Pad7)") (class "Default")
      (node (ref "DD1.2") (pin "7") (pinfunction "GND_7") (pintype "power_in"))
    )
    (net (code "70") (name "unconnected-(DD3-NC-Pad4)") (class "Default")
      (node (ref "DD3") (pin "4") (pinfunction "NC_4") (pintype "passive"))
    )
    (net (code "71") (name "unconnected-(DD3-NC-Pad5)") (class "Default")
      (node (ref "DD3") (pin "5") (pinfunction "NC_5") (pintype "passive"))
    )
    (net (code "72") (name "unconnected-(DD3-NC-Pad9)") (class "Default")
      (node (ref "DD3") (pin "9") (pinfunction "NC_9") (pintype "passive"))
    )
    (net (code "73") (name "unconnected-(DD3-NC-Pad10)") (class "Default")
      (node (ref "DD3") (pin "10") (pinfunction "NC_10") (pintype "passive"))
    )
    (net (code "74") (name "unconnected-(DD3-NC-Pad16)") (class "Default")
      (node (ref "DD3") (pin "16") (pinfunction "NC_16") (pintype "passive"))
    )
    (net (code "75") (name "unconnected-(VD9-K2-Pad2)") (class "Default")
      (node (ref "VD9") (pin "2") (pinfunction "K2_2") (pintype "passive"))
    )
    (net (code "76") (name "unconnected-(VD12-K2-Pad2)") (class "Default")
      (node (ref "VD12") (pin "2") (pinfunction "K2_2") (pintype "passive"))
    )
  )
)
